# BulbCommander1.net
KiCad netlist of a schematic drawn in Altium Designer
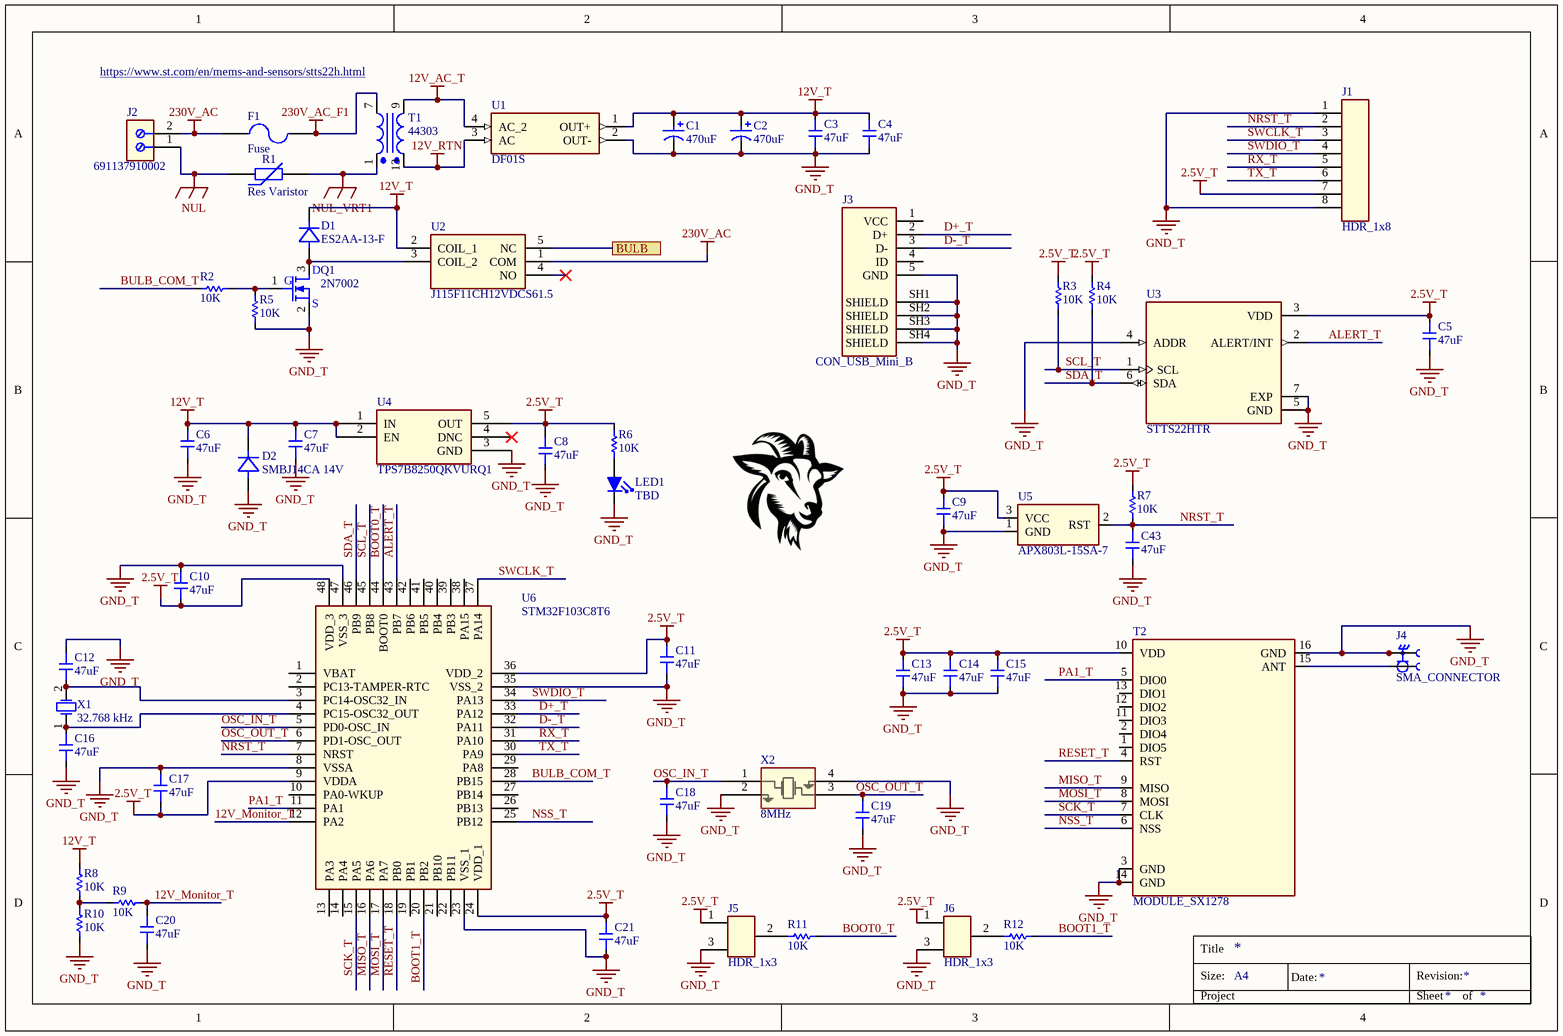
[diagram p0: BulbCommander1.SchDoc]

(export (version "E")
  (design (tool "Eeschema 10.0.6"))
  (components
    (comp (ref "C1")
      (value "470uF")
      (footprint "WCAP-ASLL_D16H17")
      (description "Capacitor_Pol_470uF")
      (fields (field (name "Comment") "Cap Pol1") (field (name "PUBLISHER") "Altium Limited"))
      (libsource (lib "BulbCommander") (part "Capacitor_Pol_470uF"))
    )
    (comp (ref "C2")
      (value "470uF")
      (footprint "WCAP-ASLL_D16H17")
      (description "Capacitor_Pol_470uF")
      (fields (field (name "Comment") "Cap Pol1") (field (name "PUBLISHER") "Altium Limited"))
      (libsource (lib "BulbCommander") (part "Capacitor_Pol_470uF"))
    )
    (comp (ref "C3")
      (value "47uF")
      (footprint "2220")
      (description "CAP CER 47uF 20% 35V X7R 2220")
      (fields (field (name "MFR") "TBD"))
      (libsource (lib "BulbCommander") (part "Capacitor_47uF_2220"))
    )
    (comp (ref "C4")
      (value "47uF")
      (footprint "2220")
      (description "CAP CER 47uF 20% 35V X7R 2220")
      (fields (field (name "MFR") "TBD"))
      (libsource (lib "BulbCommander") (part "Capacitor_47uF_2220"))
    )
    (comp (ref "C5")
      (value "47uF")
      (footprint "CASE0603")
      (description "CAP CER 47uF 20% 35V X7R 2220")
      (fields (field (name "MFR") "TBD"))
      (libsource (lib "BulbCommander") (part "Capacitor_47uF_1206"))
    )
    (comp (ref "C6")
      (value "47uF")
      (footprint "1206")
      (description "CAP CER 47uF 20% 35V X7R 2220")
      (fields (field (name "MFR") "TBD"))
      (libsource (lib "BulbCommander") (part "Capacitor_47uF_1206"))
    )
    (comp (ref "C7")
      (value "47uF")
      (footprint "1206")
      (description "CAP CER 47uF 20% 35V X7R 2220")
      (fields (field (name "MFR") "TBD"))
      (libsource (lib "BulbCommander") (part "Capacitor_47uF_1206"))
    )
    (comp (ref "C8")
      (value "47uF")
      (footprint "1206")
      (description "CAP CER 47uF 20% 35V X7R 2220")
      (fields (field (name "MFR") "TBD"))
      (libsource (lib "BulbCommander") (part "Capacitor_47uF_1206"))
    )
    (comp (ref "C9")
      (value "47uF")
      (footprint "CASE0603")
      (description "CAP CER 47uF 20% 35V X7R 2220")
      (fields (field (name "MFR") "TBD"))
      (libsource (lib "BulbCommander") (part "Capacitor_47uF_1206"))
    )
    (comp (ref "C10")
      (value "47uF")
      (footprint "CASE0603")
      (description "CAP CER 47uF 20% 35V X7R 2220")
      (fields (field (name "MFR") "TBD"))
      (libsource (lib "BulbCommander") (part "Capacitor_47uF_1206"))
    )
    (comp (ref "C11")
      (value "47uF")
      (footprint "CASE0603")
      (description "CAP CER 47uF 20% 35V X7R 2220")
      (fields (field (name "MFR") "TBD"))
      (libsource (lib "BulbCommander") (part "Capacitor_47uF_1206"))
    )
    (comp (ref "C12")
      (value "47uF")
      (footprint "CASE0603")
      (description "CAP CER 47uF 20% 35V X7R 2220")
      (fields (field (name "MFR") "TBD"))
      (libsource (lib "BulbCommander") (part "Capacitor_47uF_1206"))
    )
    (comp (ref "C13")
      (value "47uF")
      (footprint "CASE0603")
      (description "CAP CER 47uF 20% 35V X7R 2220")
      (fields (field (name "MFR") "TBD"))
      (libsource (lib "BulbCommander") (part "Capacitor_47uF_1206"))
    )
    (comp (ref "C14")
      (value "47uF")
      (footprint "CASE0603")
      (description "CAP CER 47uF 20% 35V X7R 2220")
      (fields (field (name "MFR") "TBD"))
      (libsource (lib "BulbCommander") (part "Capacitor_47uF_1206"))
    )
    (comp (ref "C15")
      (value "47uF")
      (footprint "CASE0603")
      (description "CAP CER 47uF 20% 35V X7R 2220")
      (fields (field (name "MFR") "TBD"))
      (libsource (lib "BulbCommander") (part "Capacitor_47uF_1206"))
    )
    (comp (ref "C16")
      (value "47uF")
      (footprint "CASE0603")
      (description "CAP CER 47uF 20% 35V X7R 2220")
      (fields (field (name "MFR") "TBD"))
      (libsource (lib "BulbCommander") (part "Capacitor_47uF_1206"))
    )
    (comp (ref "C17")
      (value "47uF")
      (footprint "CASE0603")
      (description "CAP CER 47uF 20% 35V X7R 2220")
      (fields (field (name "MFR") "TBD"))
      (libsource (lib "BulbCommander") (part "Capacitor_47uF_1206"))
    )
    (comp (ref "C18")
      (value "47uF")
      (footprint "CASE0603")
      (description "CAP CER 47uF 20% 35V X7R 2220")
      (fields (field (name "MFR") "TBD"))
      (libsource (lib "BulbCommander") (part "Capacitor_47uF_1206"))
    )
    (comp (ref "C19")
      (value "47uF")
      (footprint "CASE0603")
      (description "CAP CER 47uF 20% 35V X7R 2220")
      (fields (field (name "MFR") "TBD"))
      (libsource (lib "BulbCommander") (part "Capacitor_47uF_1206"))
    )
    (comp (ref "C20")
      (value "47uF")
      (footprint "CASE0603")
      (description "CAP CER 47uF 20% 35V X7R 2220")
      (fields (field (name "MFR") "TBD"))
      (libsource (lib "BulbCommander") (part "Capacitor_47uF_1206"))
    )
    (comp (ref "C21")
      (value "47uF")
      (footprint "CASE0603")
      (description "CAP CER 47uF 20% 35V X7R 2220")
      (fields (field (name "MFR") "TBD"))
      (libsource (lib "BulbCommander") (part "Capacitor_47uF_1206"))
    )
    (comp (ref "C43")
      (value "47uF")
      (footprint "CASE0603")
      (description "CAP CER 47uF 20% 35V X7R 2220")
      (fields (field (name "MFR") "TBD"))
      (libsource (lib "BulbCommander") (part "Capacitor_47uF_1206"))
    )
    (comp (ref "D1")
      (value "ES2AA-13-F")
      (footprint "SMA_DIODE")
      (description "DIODE STANDARD 50V 2A SMA")
      (fields (field (name "MFR") "Diodes Incoprated"))
      (libsource (lib "BulbCommander") (part "Diode_SMA"))
    )
    (comp (ref "D2")
      (value "SMBJ14CA 14V")
      (footprint "SMBJSeries_LTF-M")
      (description "SMBJ14CA TVS DIODE 14V")
      (libsource (lib "BulbCommander") (part "Diode_SMBJ14CA"))
    )
    (comp (ref "F1")
      (value "Fuse")
      (footprint "FUSE")
      (fields (field (name "PUBLISHER") "Altium Limited"))
      (libsource (lib "BulbCommander") (part "Fuse"))
    )
    (comp (ref "J1")
      (value "HDR_1x8")
      (footprint "Header_1x8_2.54_Male")
      (description "HDR MALE 2.54MM PCB")
      (fields (field (name "MFR") "Wurth"))
      (libsource (lib "BulbCommander") (part "HDR_1x8"))
    )
    (comp (ref "J2")
      (value "691137910002")
      (footprint "691137910002")
      (description "TERM BLOCK 2P HORIZON 7.5MM PCB")
      (fields (field (name "MFR") "Wurth"))
      (libsource (lib "BulbCommander") (part "CON_1x2"))
    )
    (comp (ref "J3")
      (value "CON_USB_Mini_B")
      (footprint "CUI_UJ2-MBH-4-SMT")
      (description "USB B mini")
      (fields (field (name "MFR") "Same Sky"))
      (libsource (lib "BulbCommander") (part "CON_USB_Mini_B"))
    )
    (comp (ref "J4")
      (value "SMA_CONNECTOR")
      (footprint "LPRS_SMA_CONNECTOR")
      (description "Straight SMA Connector")
      (fields (field (name "MP") "altium_native_batch"))
      (libsource (lib "BulbCommander") (part "SMA_CONNECTOR"))
    )
    (comp (ref "J5")
      (value "HDR_1x3")
      (footprint "Header_1x3_2.54_Male")
      (description "HDR MALE 3 x 2.54MM PCB")
      (fields (field (name "MFR") "Wurth"))
      (libsource (lib "BulbCommander") (part "HDR_1x3"))
    )
    (comp (ref "J6")
      (value "HDR_1x3")
      (footprint "Header_1x3_2.54_Male")
      (description "HDR MALE 3 x 2.54MM PCB")
      (fields (field (name "MFR") "Wurth"))
      (libsource (lib "BulbCommander") (part "HDR_1x3"))
    )
    (comp (ref "LED1")
      (value "TBD")
      (footprint "CASE0603")
      (description "Typical INFRARED GaAs LED")
      (libsource (lib "BulbCommander") (part "LED"))
    )
    (comp (ref "Q1")
      (value "2N7002")
      (footprint "SOT23-3")
      (description "MOSFET N-CH 60V 280MA SOT23-3")
      (fields (field (name "MFR") "Microchip"))
      (libsource (lib "BulbCommander") (part "Transistor_NMOS"))
    )
    (comp (ref "R1")
      (value "Res Varistor")
      (footprint "AXIAL-0.3")
      (description "Varistor (Voltage-Sensitive Resistor)")
      (fields (field (name "PUBLISHER") "Altium Limited"))
      (libsource (lib "BulbCommander") (part "Res Varistor"))
    )
    (comp (ref "R2")
      (value "10K")
      (footprint "CASE0603")
      (description "RES 10K 1% 1/10W 0603")
      (fields (field (name "MFR") "YAGEO"))
      (libsource (lib "BulbCommander") (part "Resistor_10K_0603"))
    )
    (comp (ref "R3")
      (value "10K")
      (footprint "CASE0603")
      (description "RES 10K 1% 1/10W 0603")
      (fields (field (name "MFR") "YAGEO"))
      (libsource (lib "BulbCommander") (part "Resistor_10K_0603"))
    )
    (comp (ref "R4")
      (value "10K")
      (footprint "CASE0603")
      (description "RES 10K 1% 1/10W 0603")
      (fields (field (name "MFR") "YAGEO"))
      (libsource (lib "BulbCommander") (part "Resistor_10K_0603"))
    )
    (comp (ref "R5")
      (value "10K")
      (footprint "CASE0603")
      (description "RES 10K 1% 1/10W 0603")
      (fields (field (name "MFR") "YAGEO"))
      (libsource (lib "BulbCommander") (part "Resistor_10K_0603"))
    )
    (comp (ref "R6")
      (value "10K")
      (footprint "CASE0603")
      (description "RES 10K 1% 1/10W 0603")
      (fields (field (name "MFR") "YAGEO"))
      (libsource (lib "BulbCommander") (part "Resistor_10K_0603"))
    )
    (comp (ref "R7")
      (value "10K")
      (footprint "CASE0603")
      (description "RES 10K 1% 1/10W 0603")
      (fields (field (name "MFR") "YAGEO"))
      (libsource (lib "BulbCommander") (part "Resistor_10K_0603"))
    )
    (comp (ref "R8")
      (value "10K")
      (footprint "CASE0603")
      (description "RES 10K 1% 1/10W 0603")
      (fields (field (name "MFR") "YAGEO"))
      (libsource (lib "BulbCommander") (part "Resistor_10K_0603"))
    )
    (comp (ref "R9")
      (value "10K")
      (footprint "CASE0603")
      (description "RES 10K 1% 1/10W 0603")
      (fields (field (name "MFR") "YAGEO"))
      (libsource (lib "BulbCommander") (part "Resistor_10K_0603"))
    )
    (comp (ref "R10")
      (value "10K")
      (footprint "CASE0603")
      (description "RES 10K 1% 1/10W 0603")
      (fields (field (name "MFR") "YAGEO"))
      (libsource (lib "BulbCommander") (part "Resistor_10K_0603"))
    )
    (comp (ref "R11")
      (value "10K")
      (footprint "CASE0603")
      (description "RES 10K 1% 1/10W 0603")
      (fields (field (name "MFR") "YAGEO"))
      (libsource (lib "BulbCommander") (part "Resistor_10K_0603"))
    )
    (comp (ref "R12")
      (value "10K")
      (footprint "CASE0603")
      (description "RES 10K 1% 1/10W 0603")
      (fields (field (name "MFR") "YAGEO"))
      (libsource (lib "BulbCommander") (part "Resistor_10K_0603"))
    )
    (comp (ref "T1")
      (value "44303")
      (footprint "TRAF_44303")
      (description "PCB Transformer, EI 54 x 18.8, Encapsulated Safety Isolating, 230V, 12V, 16 VA, 50Hz / 60Hz")
      (fields (field (name "MFR") "MYRRA"))
      (libsource (lib "BulbCommander") (part "TRAF_44303"))
    )
    (comp (ref "T2")
      (value "MODULE_SX1278")
      (footprint "LORA SX1278")
      (description "MODULE_SX1278 LORA 433 MHz")
      (fields (field (name "MFR") "LORA"))
      (libsource (lib "BulbCommander") (part "MODULE_SX1278"))
    )
    (comp (ref "U1")
      (value "DF01S")
      (footprint "SOT508P985X260-4N")
      (description "BRIDGE RECT 1P 100V 1.5A 4-SDIP")
      (fields (field (name "MFR") "onsemi"))
      (libsource (lib "BulbCommander") (part "RECT_DF01S"))
    )
    (comp (ref "U2")
      (value "J115F11CH12VDCS61.5")
      (footprint "J115F11CH12VDCS615U")
      (description "RELAY GEN PURPOSE SPDT 50A 12V")
      (fields (field (name "MFR") "CIT Relay and Switch"))
      (libsource (lib "BulbCommander") (part "RELAY_J115F11CH12VDCS61.5"))
    )
    (comp (ref "U3")
      (value "STTS22HTR")
      (footprint "Sensor_6-UDFN")
      (description "Low-voltage, ultralow-power, 0.5°C accuracy I²C/SMBus 3.0 temperature sensor")
      (fields (field (name "MFR") "STMicroelectronics"))
      (libsource (lib "BulbCommander") (part "SENSOR_STTS22HTR"))
    )
    (comp (ref "U4")
      (value "TPS7B8250QKVURQ1")
      (footprint "SOT_QKVURQ1_TEX")
      (fields (field (name "MFR") "Texas Instruments"))
      (libsource (lib "BulbCommander") (part "CONV_LDO_TPS7B8250QKVURQ1"))
    )
    (comp (ref "U5")
      (value "APX803L-15SA-7")
      (footprint "SOT23-3")
      (description "Supervisor Open Drain or Open Collector 1 Channel SOT-23-3")
      (fields (field (name "MFR") "Diodes Incorporated"))
      (libsource (lib "BulbCommander") (part "IC_APX803L-15SA-7"))
    )
    (comp (ref "U6")
      (value "STM32F103C8T6")
      (footprint "QFP50P900X900X160-48N")
      (description "IC MCU 32BIT 64KB FLASH 48LQFP")
      (fields (field (name "MFR") "STMicroelectronics"))
      (libsource (lib "BulbCommander") (part "IC_STM32F103C8T6"))
    )
    (comp (ref "X1")
      (value "32.768 kHz")
      (footprint "XTAL_ECS-.327-12.5-34B-C-TR")
      (description "32.768 kHz ±10ppm Crystal 12.5pF 70 kOhms 2-SMD, No Lead")
      (fields (field (name "MFR") "ECS"))
      (libsource (lib "BulbCommander") (part "Crystal_ECS-.327-12.5-34B-C-TR"))
    )
    (comp (ref "X2")
      (value "8MHz")
      (footprint "XTAL4P_ABM3B_ABR")
      (description "8 MHz Crystal")
      (fields (field (name "MFR") "Abracon"))
      (libsource (lib "BulbCommander") (part "ABM3B-8.000MHZ-10-1UT"))
    )
  )
  (nets
    (net (code "1") (name "/12V_Monitor_T") (class "Default")
      (node (ref "C20") (pin "1") (pinfunction "1_1") (pintype "passive"))
      (node (ref "R9") (pin "2") (pinfunction "2_2") (pintype "passive"))
      (node (ref "U6") (pin "12") (pinfunction "PA2_12") (pintype "passive"))
    )
    (net (code "2") (name "/ALERT_T") (class "Default")
      (node (ref "U3") (pin "2") (pinfunction "ALERT/INT_2") (pintype "output"))
      (node (ref "U6") (pin "43") (pinfunction "PB7_43") (pintype "passive"))
    )
    (net (code "3") (name "/BOOT0_T") (class "Default")
      (node (ref "R11") (pin "1") (pinfunction "1_1") (pintype "passive"))
      (node (ref "U6") (pin "44") (pinfunction "BOOT0_44") (pintype "passive"))
    )
    (net (code "4") (name "/BOOT1_T") (class "Default")
      (node (ref "R12") (pin "1") (pinfunction "1_1") (pintype "passive"))
      (node (ref "U6") (pin "20") (pinfunction "PB2_20") (pintype "passive"))
    )
    (net (code "5") (name "/BULB") (class "Default")
      (node (ref "U2") (pin "5") (pinfunction "NC_5") (pintype "passive"))
    )
    (net (code "6") (name "/BULB_COM_T") (class "Default")
      (node (ref "R2") (pin "2") (pinfunction "2_2") (pintype "passive"))
      (node (ref "U6") (pin "28") (pinfunction "PB15_28") (pintype "passive"))
    )
    (net (code "7") (name "/D+_T") (class "Default")
      (node (ref "J3") (pin "2") (pinfunction "D+_2") (pintype "passive"))
      (node (ref "U6") (pin "33") (pinfunction "PA12_33") (pintype "passive"))
    )
    (net (code "8") (name "/D-_T") (class "Default")
      (node (ref "J3") (pin "3") (pinfunction "D-_3") (pintype "passive"))
      (node (ref "U6") (pin "32") (pinfunction "PA11_32") (pintype "passive"))
    )
    (net (code "9") (name "/MISO_T") (class "Default")
      (node (ref "T2") (pin "9") (pinfunction "MISO_9") (pintype "passive"))
      (node (ref "U6") (pin "16") (pinfunction "PA6_16") (pintype "passive"))
    )
    (net (code "10") (name "/MOSI_T") (class "Default")
      (node (ref "T2") (pin "8") (pinfunction "MOSI_8") (pintype "passive"))
      (node (ref "U6") (pin "17") (pinfunction "PA7_17") (pintype "passive"))
    )
    (net (code "11") (name "/NRST_T") (class "Default")
      (node (ref "C43") (pin "2") (pinfunction "2_2") (pintype "passive"))
      (node (ref "J1") (pin "2") (pinfunction "2_2") (pintype "passive"))
      (node (ref "R7") (pin "1") (pinfunction "1_1") (pintype "passive"))
      (node (ref "U5") (pin "2") (pinfunction "RST_2") (pintype "passive"))
      (node (ref "U6") (pin "7") (pinfunction "NRST_7") (pintype "passive"))
    )
    (net (code "12") (name "/NSS_T") (class "Default")
      (node (ref "T2") (pin "6") (pinfunction "NSS_6") (pintype "passive"))
      (node (ref "U6") (pin "25") (pinfunction "PB12_25") (pintype "passive"))
    )
    (net (code "13") (name "/OSC_IN_T") (class "Default")
      (node (ref "C18") (pin "1") (pinfunction "1_1") (pintype "passive"))
      (node (ref "U6") (pin "5") (pinfunction "PD0-OSC_IN_5") (pintype "passive"))
      (node (ref "X2") (pin "1") (pinfunction "1_1") (pintype "passive"))
    )
    (net (code "14") (name "/OSC_OUT_T") (class "Default")
      (node (ref "C19") (pin "1") (pinfunction "1_1") (pintype "passive"))
      (node (ref "U6") (pin "6") (pinfunction "PD1-OSC_OUT_6") (pintype "passive"))
      (node (ref "X2") (pin "3") (pinfunction "3_3") (pintype "passive"))
    )
    (net (code "15") (name "/PA1_T") (class "Default")
      (node (ref "T2") (pin "5") (pinfunction "DIO0_5") (pintype "passive"))
      (node (ref "U6") (pin "11") (pinfunction "PA1_11") (pintype "passive"))
    )
    (net (code "16") (name "/RESET_T") (class "Default")
      (node (ref "T2") (pin "4") (pinfunction "RST_4") (pintype "passive"))
      (node (ref "U6") (pin "18") (pinfunction "PB0_18") (pintype "passive"))
    )
    (net (code "17") (name "/RX_T") (class "Default")
      (node (ref "J1") (pin "5") (pinfunction "5_5") (pintype "passive"))
      (node (ref "U6") (pin "31") (pinfunction "PA10_31") (pintype "passive"))
    )
    (net (code "18") (name "/SCK_T") (class "Default")
      (node (ref "T2") (pin "7") (pinfunction "CLK_7") (pintype "passive"))
      (node (ref "U6") (pin "15") (pinfunction "PA5_15") (pintype "passive"))
    )
    (net (code "19") (name "/SCL_T") (class "Default")
      (node (ref "R3") (pin "1") (pinfunction "1_1") (pintype "passive"))
      (node (ref "U3") (pin "1") (pinfunction "SCL_1") (pintype "input"))
      (node (ref "U6") (pin "45") (pinfunction "PB8_45") (pintype "passive"))
    )
    (net (code "20") (name "/SDA_T") (class "Default")
      (node (ref "R4") (pin "1") (pinfunction "1_1") (pintype "passive"))
      (node (ref "U3") (pin "6") (pinfunction "SDA_6") (pintype "bidirectional"))
      (node (ref "U6") (pin "46") (pinfunction "PB9_46") (pintype "passive"))
    )
    (net (code "21") (name "/SWCLK_T") (class "Default")
      (node (ref "J1") (pin "3") (pinfunction "3_3") (pintype "passive"))
      (node (ref "U6") (pin "37") (pinfunction "PA14_37") (pintype "passive"))
    )
    (net (code "22") (name "/SWDIO_T") (class "Default")
      (node (ref "J1") (pin "4") (pinfunction "4_4") (pintype "passive"))
      (node (ref "U6") (pin "34") (pinfunction "PA13_34") (pintype "passive"))
    )
    (net (code "23") (name "/TX_T") (class "Default")
      (node (ref "J1") (pin "6") (pinfunction "6_6") (pintype "passive"))
      (node (ref "U6") (pin "30") (pinfunction "PA9_30") (pintype "passive"))
    )
    (net (code "24") (name "2.5V_T") (class "Default")
      (node (ref "C10") (pin "1") (pinfunction "1_1") (pintype "passive"))
      (node (ref "C11") (pin "2") (pinfunction "2_2") (pintype "passive"))
      (node (ref "C13") (pin "2") (pinfunction "2_2") (pintype "passive"))
      (node (ref "C14") (pin "2") (pinfunction "2_2") (pintype "passive"))
      (node (ref "C15") (pin "2") (pinfunction "2_2") (pintype "passive"))
      (node (ref "C17") (pin "2") (pinfunction "2_2") (pintype "passive"))
      (node (ref "C21") (pin "2") (pinfunction "2_2") (pintype "passive"))
      (node (ref "C5") (pin "2") (pinfunction "2_2") (pintype "passive"))
      (node (ref "C8") (pin "2") (pinfunction "2_2") (pintype "passive"))
      (node (ref "C9") (pin "2") (pinfunction "2_2") (pintype "passive"))
      (node (ref "J1") (pin "7") (pinfunction "7_7") (pintype "passive"))
      (node (ref "J5") (pin "1") (pinfunction "1_1") (pintype "passive"))
      (node (ref "J6") (pin "1") (pinfunction "1_1") (pintype "passive"))
      (node (ref "R3") (pin "2") (pinfunction "2_2") (pintype "passive"))
      (node (ref "R4") (pin "2") (pinfunction "2_2") (pintype "passive"))
      (node (ref "R6") (pin "2") (pinfunction "2_2") (pintype "passive"))
      (node (ref "R7") (pin "2") (pinfunction "2_2") (pintype "passive"))
      (node (ref "T2") (pin "10") (pinfunction "VDD_10") (pintype "passive"))
      (node (ref "U3") (pin "3") (pinfunction "VDD_3") (pintype "power_in"))
      (node (ref "U4") (pin "5") (pinfunction "OUT_5") (pintype "passive"))
      (node (ref "U5") (pin "3") (pinfunction "VCC_3") (pintype "passive"))
      (node (ref "U6") (pin "24") (pinfunction "VDD_1_24") (pintype "passive"))
      (node (ref "U6") (pin "36") (pinfunction "VDD_2_36") (pintype "passive"))
      (node (ref "U6") (pin "48") (pinfunction "VDD_3_48") (pintype "passive"))
      (node (ref "U6") (pin "9") (pinfunction "VDDA_9") (pintype "passive"))
    )
    (net (code "25") (name "12V_AC_T") (class "Default")
      (node (ref "T1") (pin "9") (pinfunction "PRI1_9") (pintype "passive"))
      (node (ref "U1") (pin "4") (pinfunction "AC_2_4") (pintype "input"))
    )
    (net (code "26") (name "12V_RTN") (class "Default")
      (node (ref "T1") (pin "13") (pinfunction "SEC_13") (pintype "passive"))
      (node (ref "U1") (pin "3") (pinfunction "AC_3") (pintype "input"))
    )
    (net (code "27") (name "12V_T") (class "Default")
      (node (ref "C1") (pin "1") (pinfunction "1_1") (pintype "passive"))
      (node (ref "C2") (pin "1") (pinfunction "1_1") (pintype "passive"))
      (node (ref "C3") (pin "2") (pinfunction "2_2") (pintype "passive"))
      (node (ref "C4") (pin "2") (pinfunction "2_2") (pintype "passive"))
      (node (ref "C6") (pin "2") (pinfunction "2_2") (pintype "passive"))
      (node (ref "C7") (pin "2") (pinfunction "2_2") (pintype "passive"))
      (node (ref "D1") (pin "1") (pinfunction "1_1") (pintype "passive"))
      (node (ref "D2") (pin "1") (pinfunction "1_1") (pintype "passive"))
      (node (ref "R8") (pin "2") (pinfunction "2_2") (pintype "passive"))
      (node (ref "U1") (pin "1") (pinfunction "OUT+_1") (pintype "output"))
      (node (ref "U2") (pin "2") (pinfunction "COIL_1_2") (pintype "passive"))
      (node (ref "U4") (pin "1") (pinfunction "IN_1") (pintype "passive"))
      (node (ref "U4") (pin "2") (pinfunction "EN_2") (pintype "passive"))
    )
    (net (code "28") (name "230V_AC") (class "Default")
      (node (ref "F1") (pin "1") (pinfunction "1_1") (pintype "passive"))
      (node (ref "J2") (pin "2") (pinfunction "2_2") (pintype "passive"))
      (node (ref "U2") (pin "1") (pinfunction "COM_1") (pintype "passive"))
    )
    (net (code "29") (name "230V_AC_F1") (class "Default")
      (node (ref "F1") (pin "2") (pinfunction "2_2") (pintype "passive"))
      (node (ref "T1") (pin "7") (pinfunction "PRI1_7") (pintype "passive"))
    )
    (net (code "30") (name "GND_T") (class "Default")
      (node (ref "C1") (pin "2") (pinfunction "2_2") (pintype "passive"))
      (node (ref "C10") (pin "2") (pinfunction "2_2") (pintype "passive"))
      (node (ref "C11") (pin "1") (pinfunction "1_1") (pintype "passive"))
      (node (ref "C12") (pin "2") (pinfunction "2_2") (pintype "passive"))
      (node (ref "C13") (pin "1") (pinfunction "1_1") (pintype "passive"))
      (node (ref "C14") (pin "1") (pinfunction "1_1") (pintype "passive"))
      (node (ref "C15") (pin "1") (pinfunction "1_1") (pintype "passive"))
      (node (ref "C16") (pin "2") (pinfunction "2_2") (pintype "passive"))
      (node (ref "C17") (pin "1") (pinfunction "1_1") (pintype "passive"))
      (node (ref "C18") (pin "2") (pinfunction "2_2") (pintype "passive"))
      (node (ref "C19") (pin "2") (pinfunction "2_2") (pintype "passive"))
      (node (ref "C2") (pin "2") (pinfunction "2_2") (pintype "passive"))
      (node (ref "C20") (pin "2") (pinfunction "2_2") (pintype "passive"))
      (node (ref "C21") (pin "1") (pinfunction "1_1") (pintype "passive"))
      (node (ref "C3") (pin "1") (pinfunction "1_1") (pintype "passive"))
      (node (ref "C4") (pin "1") (pinfunction "1_1") (pintype "passive"))
      (node (ref "C43") (pin "1") (pinfunction "1_1") (pintype "passive"))
      (node (ref "C5") (pin "1") (pinfunction "1_1") (pintype "passive"))
      (node (ref "C6") (pin "1") (pinfunction "1_1") (pintype "passive"))
      (node (ref "C7") (pin "1") (pinfunction "1_1") (pintype "passive"))
      (node (ref "C8") (pin "1") (pinfunction "1_1") (pintype "passive"))
      (node (ref "C9") (pin "1") (pinfunction "1_1") (pintype "passive"))
      (node (ref "D2") (pin "2") (pinfunction "2_2") (pintype "passive"))
      (node (ref "J1") (pin "1") (pinfunction "1_1") (pintype "passive"))
      (node (ref "J1") (pin "8") (pinfunction "8_8") (pintype "passive"))
      (node (ref "J3") (pin "5") (pinfunction "GND_5") (pintype "passive"))
      (node (ref "J3") (pin "SH1") (pinfunction "SHIELD_SH1") (pintype "passive"))
      (node (ref "J3") (pin "SH2") (pinfunction "SHIELD_SH2") (pintype "passive"))
      (node (ref "J3") (pin "SH3") (pinfunction "SHIELD_SH3") (pintype "passive"))
      (node (ref "J3") (pin "SH4") (pinfunction "SHIELD_SH4") (pintype "passive"))
      (node (ref "J4") (pin "G1") (pinfunction "2_G1") (pintype "passive"))
      (node (ref "J4") (pin "G2") (pinfunction "2_G2") (pintype "passive"))
      (node (ref "J4") (pin "G3") (pinfunction "2_G3") (pintype "passive"))
      (node (ref "J4") (pin "G4") (pinfunction "2_G4") (pintype "passive"))
      (node (ref "J5") (pin "3") (pinfunction "3_3") (pintype "passive"))
      (node (ref "J6") (pin "3") (pinfunction "3_3") (pintype "passive"))
      (node (ref "LED1") (pin "2") (pinfunction "K_2") (pintype "passive"))
      (node (ref "Q1") (pin "2") (pinfunction "S_2") (pintype "passive"))
      (node (ref "R10") (pin "1") (pinfunction "1_1") (pintype "passive"))
      (node (ref "R5") (pin "1") (pinfunction "1_1") (pintype "passive"))
      (node (ref "T2") (pin "14") (pinfunction "GND_14") (pintype "passive"))
      (node (ref "T2") (pin "16") (pinfunction "GND_16") (pintype "passive"))
      (node (ref "T2") (pin "3") (pinfunction "GND_3") (pintype "passive"))
      (node (ref "U1") (pin "2") (pinfunction "OUT-_2") (pintype "output"))
      (node (ref "U3") (pin "4") (pinfunction "ADDR_4") (pintype "input"))
      (node (ref "U3") (pin "5") (pinfunction "GND_5") (pintype "power_in"))
      (node (ref "U3") (pin "7") (pinfunction "EXP_7") (pintype "passive"))
      (node (ref "U4") (pin "3") (pinfunction "GND_3") (pintype "passive"))
      (node (ref "U5") (pin "1") (pinfunction "GND_1") (pintype "passive"))
      (node (ref "U6") (pin "23") (pinfunction "VSS_1_23") (pintype "passive"))
      (node (ref "U6") (pin "35") (pinfunction "VSS_2_35") (pintype "passive"))
      (node (ref "U6") (pin "47") (pinfunction "VSS_3_47") (pintype "passive"))
      (node (ref "U6") (pin "8") (pinfunction "VSSA_8") (pintype "passive"))
      (node (ref "X2") (pin "2") (pinfunction "2_2") (pintype "passive"))
      (node (ref "X2") (pin "4") (pinfunction "4_4") (pintype "passive"))
    )
    (net (code "31") (name "NUL") (class "Default")
      (node (ref "J2") (pin "1") (pinfunction "1_1") (pintype "passive"))
      (node (ref "R1") (pin "1") (pinfunction "1_1") (pintype "passive"))
    )
    (net (code "32") (name "NUL_VRT1") (class "Default")
      (node (ref "R1") (pin "2") (pinfunction "2_2") (pintype "passive"))
      (node (ref "T1") (pin "1") (pinfunction "PRI1_1") (pintype "passive"))
    )
    (net (code "33") (name "Net-(J5-Pad2)") (class "Default")
      (node (ref "J5") (pin "2") (pinfunction "2_2") (pintype "passive"))
      (node (ref "R11") (pin "2") (pinfunction "2_2") (pintype "passive"))
    )
    (net (code "34") (name "Net-(J6-Pad2)") (class "Default")
      (node (ref "J6") (pin "2") (pinfunction "2_2") (pintype "passive"))
      (node (ref "R12") (pin "2") (pinfunction "2_2") (pintype "passive"))
    )
    (net (code "35") (name "Net-(LED1-A)") (class "Default")
      (node (ref "LED1") (pin "1") (pinfunction "A_1") (pintype "passive"))
      (node (ref "R6") (pin "1") (pinfunction "1_1") (pintype "passive"))
    )
    (net (code "36") (name "Net-(Q1-D)") (class "Default")
      (node (ref "D1") (pin "2") (pinfunction "2_2") (pintype "passive"))
      (node (ref "Q1") (pin "3") (pinfunction "D_3") (pintype "passive"))
      (node (ref "U2") (pin "3") (pinfunction "COIL_2_3") (pintype "passive"))
    )
    (net (code "37") (name "Net-(Q1-G)") (class "Default")
      (node (ref "Q1") (pin "1") (pinfunction "G_1") (pintype "passive"))
      (node (ref "R2") (pin "1") (pinfunction "1_1") (pintype "passive"))
      (node (ref "R5") (pin "2") (pinfunction "2_2") (pintype "passive"))
    )
    (net (code "38") (name "Net-(R10-Pad2)") (class "Default")
      (node (ref "R10") (pin "2") (pinfunction "2_2") (pintype "passive"))
      (node (ref "R8") (pin "1") (pinfunction "1_1") (pintype "passive"))
      (node (ref "R9") (pin "1") (pinfunction "1_1") (pintype "passive"))
    )
    (net (code "39") (name "Net-(T2-ANT)") (class "Default")
      (node (ref "J4") (pin "1") (pinfunction "1_1") (pintype "passive"))
      (node (ref "T2") (pin "15") (pinfunction "ANT_15") (pintype "passive"))
    )
    (net (code "40") (name "Net-(U6-PC14-OSC32_IN)") (class "Default")
      (node (ref "C12") (pin "1") (pinfunction "1_1") (pintype "passive"))
      (node (ref "U6") (pin "3") (pinfunction "PC14-OSC32_IN_3") (pintype "passive"))
      (node (ref "X1") (pin "2") (pinfunction "OSC2_2") (pintype "passive"))
    )
    (net (code "41") (name "Net-(U6-PC15-OSC32_OUT)") (class "Default")
      (node (ref "C16") (pin "1") (pinfunction "1_1") (pintype "passive"))
      (node (ref "U6") (pin "4") (pinfunction "PC15-OSC32_OUT_4") (pintype "passive"))
      (node (ref "X1") (pin "1") (pinfunction "OSC1_1") (pintype "passive"))
    )
    (net (code "42") (name "unconnected-(J3-ID-Pad4)") (class "Default")
      (node (ref "J3") (pin "4") (pinfunction "ID_4") (pintype "passive"))
    )
    (net (code "43") (name "unconnected-(J3-VCC-Pad1)") (class "Default")
      (node (ref "J3") (pin "1") (pinfunction "VCC_1") (pintype "passive"))
    )
    (net (code "44") (name "unconnected-(T2-DIO1-Pad13)") (class "Default")
      (node (ref "T2") (pin "13") (pinfunction "DIO1_13") (pintype "passive"))
    )
    (net (code "45") (name "unconnected-(T2-DIO2-Pad12)") (class "Default")
      (node (ref "T2") (pin "12") (pinfunction "DIO2_12") (pintype "passive"))
    )
    (net (code "46") (name "unconnected-(T2-DIO3-Pad11)") (class "Default")
      (node (ref "T2") (pin "11") (pinfunction "DIO3_11") (pintype "passive"))
    )
    (net (code "47") (name "unconnected-(T2-DIO4-Pad2)") (class "Default")
      (node (ref "T2") (pin "2") (pinfunction "DIO4_2") (pintype "passive"))
    )
    (net (code "48") (name "unconnected-(T2-DIO5-Pad1)") (class "Default")
      (node (ref "T2") (pin "1") (pinfunction "DIO5_1") (pintype "passive"))
    )
    (net (code "49") (name "unconnected-(U2-NO-Pad4)") (class "Default")
      (node (ref "U2") (pin "4") (pinfunction "NO_4") (pintype "passive+no_connect"))
    )
    (net (code "50") (name "unconnected-(U4-DNC-Pad4)") (class "Default")
      (node (ref "U4") (pin "4") (pinfunction "DNC_4") (pintype "passive+no_connect"))
    )
    (net (code "51") (name "unconnected-(U6-PA0-WKUP-Pad10)") (class "Default")
      (node (ref "U6") (pin "10") (pinfunction "PA0-WKUP_10") (pintype "passive"))
    )
    (net (code "52") (name "unconnected-(U6-PA3-Pad13)") (class "Default")
      (node (ref "U6") (pin "13") (pinfunction "PA3_13") (pintype "passive"))
    )
    (net (code "53") (name "unconnected-(U6-PA4-Pad14)") (class "Default")
      (node (ref "U6") (pin "14") (pinfunction "PA4_14") (pintype "passive"))
    )
    (net (code "54") (name "unconnected-(U6-PA8-Pad29)") (class "Default")
      (node (ref "U6") (pin "29") (pinfunction "PA8_29") (pintype "passive"))
    )
    (net (code "55") (name "unconnected-(U6-PA15-Pad38)") (class "Default")
      (node (ref "U6") (pin "38") (pinfunction "PA15_38") (pintype "passive"))
    )
    (net (code "56") (name "unconnected-(U6-PB1-Pad19)") (class "Default")
      (node (ref "U6") (pin "19") (pinfunction "PB1_19") (pintype "passive"))
    )
    (net (code "57") (name "unconnected-(U6-PB3-Pad39)") (class "Default")
      (node (ref "U6") (pin "39") (pinfunction "PB3_39") (pintype "passive"))
    )
    (net (code "58") (name "unconnected-(U6-PB4-Pad40)") (class "Default")
      (node (ref "U6") (pin "40") (pinfunction "PB4_40") (pintype "passive"))
    )
    (net (code "59") (name "unconnected-(U6-PB5-Pad41)") (class "Default")
      (node (ref "U6") (pin "41") (pinfunction "PB5_41") (pintype "passive"))
    )
    (net (code "60") (name "unconnected-(U6-PB6-Pad42)") (class "Default")
      (node (ref "U6") (pin "42") (pinfunction "PB6_42") (pintype "passive"))
    )
    (net (code "61") (name "unconnected-(U6-PB10-Pad21)") (class "Default")
      (node (ref "U6") (pin "21") (pinfunction "PB10_21") (pintype "passive"))
    )
    (net (code "62") (name "unconnected-(U6-PB11-Pad22)") (class "Default")
      (node (ref "U6") (pin "22") (pinfunction "PB11_22") (pintype "passive"))
    )
    (net (code "63") (name "unconnected-(U6-PB13-Pad26)") (class "Default")
      (node (ref "U6") (pin "26") (pinfunction "PB13_26") (pintype "passive"))
    )
    (net (code "64") (name "unconnected-(U6-PB14-Pad27)") (class "Default")
      (node (ref "U6") (pin "27") (pinfunction "PB14_27") (pintype "passive"))
    )
    (net (code "65") (name "unconnected-(U6-PC13-TAMPER-RTC-Pad2)") (class "Default")
      (node (ref "U6") (pin "2") (pinfunction "PC13-TAMPER-RTC_2") (pintype "passive"))
    )
    (net (code "66") (name "unconnected-(U6-VBAT-Pad1)") (class "Default")
      (node (ref "U6") (pin "1") (pinfunction "VBAT_1") (pintype "passive"))
    )
  )
)
